# UI_BUTTON_LED.net
KiCad netlist of a schematic drawn in Altium Designer
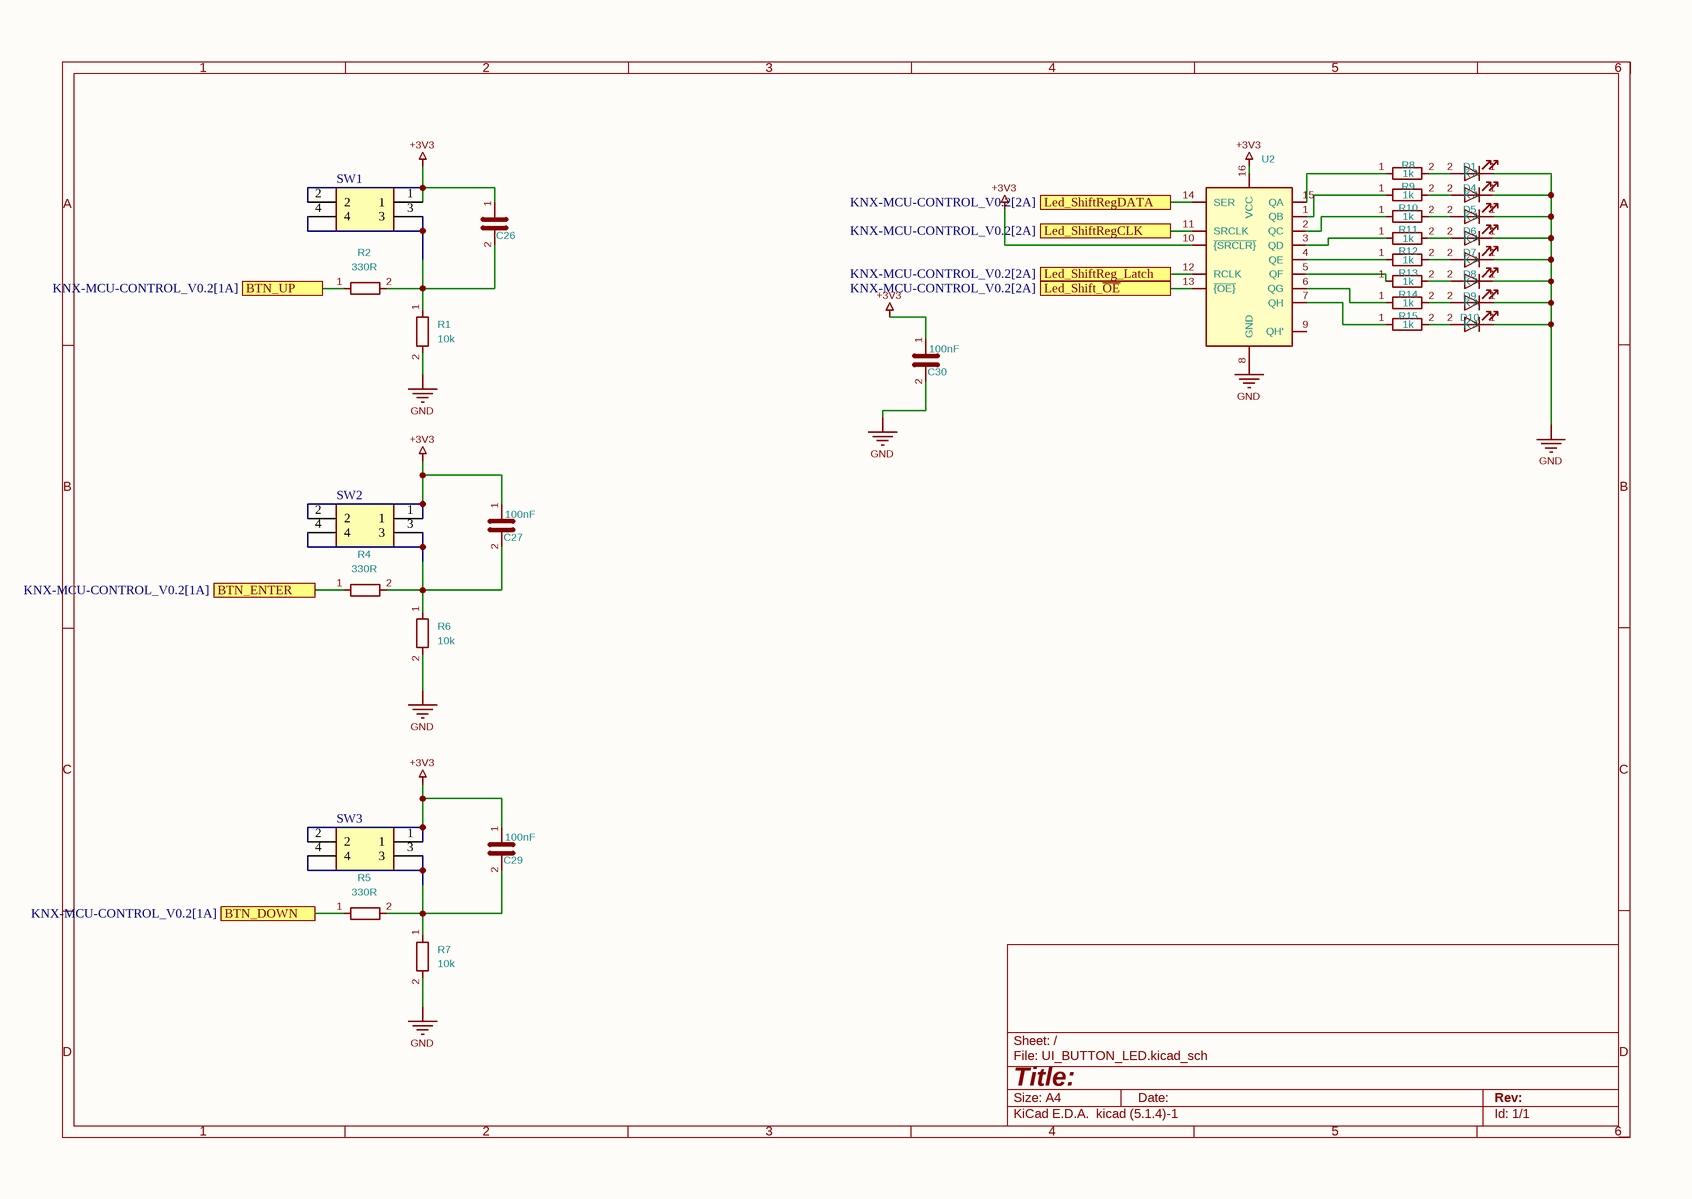
[diagram p0: UI_BUTTON_LED.SchDoc]

(export (version "E")
  (design (tool "Eeschema 10.0.6"))
  (components
    (comp (ref "C26")
      (value "100nF")
      (footprint "C_0603_1608Metric")
      (fields
        (field (name "MANUFACTURER PART NUMBER") "CC0603KRX7R9BB104")
        (field (name "MANUFACTURER") "YAGEO")
      )
      (libsource (lib "*") (part "C_3"))
    )
    (comp (ref "C27")
      (value "100nF")
      (footprint "C_0603_1608Metric")
      (fields
        (field (name "MANUFACTURER PART NUMBER") "CC0603KRX7R9BB104")
        (field (name "MANUFACTURER") "YAGEO")
      )
      (libsource (lib "*") (part "C_3"))
    )
    (comp (ref "C29")
      (value "100nF")
      (footprint "C_0603_1608Metric")
      (fields
        (field (name "MANUFACTURER PART NUMBER") "CC0603KRX7R9BB104")
        (field (name "MANUFACTURER") "YAGEO")
      )
      (libsource (lib "*") (part "C_3"))
    )
    (comp (ref "C30")
      (value "100nF")
      (footprint "C_0603_1608Metric")
      (fields
        (field (name "MANUFACTURER PART NUMBER") "CC0603KRX7R9BB104")
        (field (name "MANUFACTURER") "YAGEO")
      )
      (libsource (lib "*") (part "C_1"))
    )
    (comp (ref "D1")
      (value "LED")
      (footprint "LED_0603_1608Metric")
      (fields
        (field (name "MANUFACTURER") "LITEON")
        (field (name "MANUFACTURER PART NUMBER") "LTST-C190KFKT-5A")
      )
      (libsource (lib "Device") (part "LED"))
    )
    (comp (ref "D4")
      (value "LED")
      (footprint "LED_0603_1608Metric")
      (fields
        (field (name "MANUFACTURER") "LITEON")
        (field (name "MANUFACTURER PART NUMBER") "LTST-C190KFKT-5A")
      )
      (libsource (lib "Device") (part "LED"))
    )
    (comp (ref "D5")
      (value "LED")
      (footprint "LED_0603_1608Metric")
      (fields
        (field (name "MANUFACTURER") "LITEON")
        (field (name "MANUFACTURER PART NUMBER") "LTST-C190KFKT-5A")
      )
      (libsource (lib "Device") (part "LED"))
    )
    (comp (ref "D6")
      (value "LED")
      (footprint "LED_0603_1608Metric")
      (fields
        (field (name "MANUFACTURER") "LITEON")
        (field (name "MANUFACTURER PART NUMBER") "LTST-C190KFKT-5A")
      )
      (libsource (lib "Device") (part "LED"))
    )
    (comp (ref "D7")
      (value "LED")
      (footprint "LED_0603_1608Metric")
      (fields
        (field (name "MANUFACTURER") "LITEON")
        (field (name "MANUFACTURER PART NUMBER") "LTST-C190KFKT-5A")
      )
      (libsource (lib "Device") (part "LED"))
    )
    (comp (ref "D8")
      (value "LED")
      (footprint "LED_0603_1608Metric")
      (fields
        (field (name "MANUFACTURER") "LITEON")
        (field (name "MANUFACTURER PART NUMBER") "LTST-C190KFKT-5A")
      )
      (libsource (lib "Device") (part "LED"))
    )
    (comp (ref "D9")
      (value "LED")
      (footprint "LED_0603_1608Metric")
      (fields
        (field (name "MANUFACTURER") "LITEON")
        (field (name "MANUFACTURER PART NUMBER") "LTST-C190KFKT-5A")
      )
      (libsource (lib "Device") (part "LED"))
    )
    (comp (ref "D10")
      (value "LED")
      (footprint "LED_0603_1608Metric")
      (fields
        (field (name "MANUFACTURER") "LITEON")
        (field (name "MANUFACTURER PART NUMBER") "LTST-C190KFKT-5A")
      )
      (libsource (lib "Device") (part "LED"))
    )
    (comp (ref "R1")
      (value "10k")
      (footprint "R_0603_1608Metric")
      (fields (field (name "MANUFACTURER") "FOJAN") (field (name "MANUFACTURER PART NUMBER") "FRC0603J103TS"))
      (libsource (lib "Device") (part "R"))
    )
    (comp (ref "R2")
      (value "330R")
      (footprint "R_0603_1608Metric")
      (fields
        (field (name "MANUFACTURER") "FOJAN")
        (field (name "MANUFACTURER PART NUMBER") "FRC0603J331 TS")
      )
      (libsource (lib "") (part "R_1"))
    )
    (comp (ref "R4")
      (value "330R")
      (footprint "R_0603_1608Metric")
      (fields
        (field (name "MANUFACTURER") "FOJAN")
        (field (name "MANUFACTURER PART NUMBER") "FRC0603J331 TS")
      )
      (libsource (lib "") (part "R_1"))
    )
    (comp (ref "R5")
      (value "330R")
      (footprint "R_0603_1608Metric")
      (fields
        (field (name "MANUFACTURER") "FOJAN")
        (field (name "MANUFACTURER PART NUMBER") "FRC0603J331 TS")
      )
      (libsource (lib "") (part "R_1"))
    )
    (comp (ref "R6")
      (value "10k")
      (footprint "R_0603_1608Metric")
      (fields (field (name "MANUFACTURER") "FOJAN") (field (name "MANUFACTURER PART NUMBER") "FRC0603J103TS"))
      (libsource (lib "Device") (part "R"))
    )
    (comp (ref "R7")
      (value "10k")
      (footprint "R_0603_1608Metric")
      (fields (field (name "MANUFACTURER") "FOJAN") (field (name "MANUFACTURER PART NUMBER") "FRC0603J103TS"))
      (libsource (lib "Device") (part "R"))
    )
    (comp (ref "R8")
      (value "1k")
      (footprint "R_0603_1608Metric")
      (fields
        (field (name "MANUFACTURER") "YAGEO")
        (field (name "MANUFACTURER PART NUMBER") "RC0603JR-071KL")
      )
      (libsource (lib "") (part "R_1"))
    )
    (comp (ref "R9")
      (value "1k")
      (footprint "R_0603_1608Metric")
      (fields
        (field (name "MANUFACTURER") "YAGEO")
        (field (name "MANUFACTURER PART NUMBER") "RC0603JR-071KL")
      )
      (libsource (lib "") (part "R_1"))
    )
    (comp (ref "R10")
      (value "1k")
      (footprint "R_0603_1608Metric")
      (fields
        (field (name "MANUFACTURER") "YAGEO")
        (field (name "MANUFACTURER PART NUMBER") "RC0603JR-071KL")
      )
      (libsource (lib "") (part "R_1"))
    )
    (comp (ref "R11")
      (value "1k")
      (footprint "R_0603_1608Metric")
      (fields
        (field (name "MANUFACTURER") "YAGEO")
        (field (name "MANUFACTURER PART NUMBER") "RC0603JR-071KL")
      )
      (libsource (lib "") (part "R_1"))
    )
    (comp (ref "R12")
      (value "1k")
      (footprint "R_0603_1608Metric")
      (fields
        (field (name "MANUFACTURER") "YAGEO")
        (field (name "MANUFACTURER PART NUMBER") "RC0603JR-071KL")
      )
      (libsource (lib "") (part "R_1"))
    )
    (comp (ref "R13")
      (value "1k")
      (footprint "R_0603_1608Metric")
      (fields
        (field (name "MANUFACTURER") "YAGEO")
        (field (name "MANUFACTURER PART NUMBER") "RC0603JR-071KL")
      )
      (libsource (lib "") (part "R_1"))
    )
    (comp (ref "R14")
      (value "1k")
      (footprint "R_0603_1608Metric")
      (fields
        (field (name "MANUFACTURER") "YAGEO")
        (field (name "MANUFACTURER PART NUMBER") "RC0603JR-071KL")
      )
      (libsource (lib "") (part "R_1"))
    )
    (comp (ref "R15")
      (value "1k")
      (footprint "R_0603_1608Metric")
      (fields
        (field (name "MANUFACTURER") "YAGEO")
        (field (name "MANUFACTURER PART NUMBER") "RC0603JR-071KL")
      )
      (libsource (lib "") (part "R_1"))
    )
    (comp (ref "SW1")
      (value "TSA06141-225B532CA-3C00")
      (footprint "SamacSys:TL1105")
      (description "Through Hole-4P,8.2x7.6mm")
      (fields (field (name "MANUFACTURER") "Khon"))
      (libsource (lib "*") (part "TL1105BF160Q"))
    )
    (comp (ref "SW2")
      (value "TSA06141-225B532CA-3C00")
      (footprint "SamacSys:TL1105")
      (description "Through Hole-4P,8.2x7.6mm")
      (fields (field (name "MANUFACTURER") "Khon"))
      (libsource (lib "*") (part "TL1105BF160Q"))
    )
    (comp (ref "SW3")
      (value "TSA06141-225B532CA-3C00")
      (footprint "SamacSys:TL1105")
      (description "Through Hole-4P,8.2x7.6mm")
      (fields (field (name "MANUFACTURER") "Khon"))
      (libsource (lib "*") (part "TL1105BF160Q"))
    )
    (comp (ref "U2")
      (value "74HC595PW,118")
      (footprint "TSSOP-16_4.4x5mm_P0.65mm")
      (fields (field (name "MANUFACTURER") "Nexperia"))
      (libsource (lib "74xx") (part "74HC595"))
    )
  )
  (nets
    (net (code "1") (name "+3V3") (class "Default")
      (node (ref "C26") (pin "1") (pinfunction "1_1") (pintype "passive"))
      (node (ref "C27") (pin "1") (pinfunction "1_1") (pintype "passive"))
      (node (ref "C29") (pin "1") (pinfunction "1_1") (pintype "passive"))
      (node (ref "C30") (pin "1") (pinfunction "1_1") (pintype "passive"))
      (node (ref "SW1") (pin "1") (pinfunction "1_1") (pintype "passive"))
      (node (ref "SW1") (pin "2") (pinfunction "2_2") (pintype "passive"))
      (node (ref "SW2") (pin "1") (pinfunction "1_1") (pintype "passive"))
      (node (ref "SW2") (pin "2") (pinfunction "2_2") (pintype "passive"))
      (node (ref "SW3") (pin "1") (pinfunction "1_1") (pintype "passive"))
      (node (ref "SW3") (pin "2") (pinfunction "2_2") (pintype "passive"))
      (node (ref "U2") (pin "10") (pinfunction "~{{SRCLR}}_10") (pintype "passive"))
      (node (ref "U2") (pin "16") (pinfunction "VCC_16") (pintype "passive"))
    )
    (net (code "2") (name "/BTN_DOWN") (class "Default")
      (node (ref "R5") (pin "1") (pinfunction "1_1") (pintype "passive"))
    )
    (net (code "3") (name "/BTN_ENTER") (class "Default")
      (node (ref "R4") (pin "1") (pinfunction "1_1") (pintype "passive"))
    )
    (net (code "4") (name "/BTN_UP") (class "Default")
      (node (ref "R2") (pin "1") (pinfunction "1_1") (pintype "passive"))
    )
    (net (code "5") (name "/Led_ShiftRegCLK") (class "Default")
      (node (ref "U2") (pin "11") (pinfunction "SRCLK_11") (pintype "passive"))
    )
    (net (code "6") (name "/Led_ShiftRegDATA") (class "Default")
      (node (ref "U2") (pin "14") (pinfunction "SER_14") (pintype "passive"))
    )
    (net (code "7") (name "/Led_ShiftReg_Latch") (class "Default")
      (node (ref "U2") (pin "12") (pinfunction "RCLK_12") (pintype "passive"))
    )
    (net (code "8") (name "/Led_Shift_~{OE}") (class "Default")
      (node (ref "U2") (pin "13") (pinfunction "~{{OE}}_13") (pintype "passive"))
    )
    (net (code "9") (name "GND") (class "Default")
      (node (ref "C30") (pin "2") (pinfunction "2_2") (pintype "passive"))
      (node (ref "D1") (pin "1") (pinfunction "K_1") (pintype "passive"))
      (node (ref "D10") (pin "1") (pinfunction "K_1") (pintype "passive"))
      (node (ref "D4") (pin "1") (pinfunction "K_1") (pintype "passive"))
      (node (ref "D5") (pin "1") (pinfunction "K_1") (pintype "passive"))
      (node (ref "D6") (pin "1") (pinfunction "K_1") (pintype "passive"))
      (node (ref "D7") (pin "1") (pinfunction "K_1") (pintype "passive"))
      (node (ref "D8") (pin "1") (pinfunction "K_1") (pintype "passive"))
      (node (ref "D9") (pin "1") (pinfunction "K_1") (pintype "passive"))
      (node (ref "R1") (pin "2") (pinfunction "2_2") (pintype "passive"))
      (node (ref "R6") (pin "2") (pinfunction "2_2") (pintype "passive"))
      (node (ref "R7") (pin "2") (pinfunction "2_2") (pintype "passive"))
      (node (ref "U2") (pin "8") (pinfunction "GND_8") (pintype "passive"))
    )
    (net (code "10") (name "Net-(C26-Pad2)") (class "Default")
      (node (ref "C26") (pin "2") (pinfunction "2_2") (pintype "passive"))
      (node (ref "R1") (pin "1") (pinfunction "1_1") (pintype "passive"))
      (node (ref "R2") (pin "2") (pinfunction "2_2") (pintype "passive"))
      (node (ref "SW1") (pin "3") (pinfunction "3_3") (pintype "passive"))
      (node (ref "SW1") (pin "4") (pinfunction "4_4") (pintype "passive"))
    )
    (net (code "11") (name "Net-(C27-Pad2)") (class "Default")
      (node (ref "C27") (pin "2") (pinfunction "2_2") (pintype "passive"))
      (node (ref "R4") (pin "2") (pinfunction "2_2") (pintype "passive"))
      (node (ref "R6") (pin "1") (pinfunction "1_1") (pintype "passive"))
      (node (ref "SW2") (pin "3") (pinfunction "3_3") (pintype "passive"))
      (node (ref "SW2") (pin "4") (pinfunction "4_4") (pintype "passive"))
    )
    (net (code "12") (name "Net-(C29-Pad2)") (class "Default")
      (node (ref "C29") (pin "2") (pinfunction "2_2") (pintype "passive"))
      (node (ref "R5") (pin "2") (pinfunction "2_2") (pintype "passive"))
      (node (ref "R7") (pin "1") (pinfunction "1_1") (pintype "passive"))
      (node (ref "SW3") (pin "3") (pinfunction "3_3") (pintype "passive"))
      (node (ref "SW3") (pin "4") (pinfunction "4_4") (pintype "passive"))
    )
    (net (code "13") (name "Net-(D1-A)") (class "Default")
      (node (ref "D1") (pin "2") (pinfunction "A_2") (pintype "passive"))
      (node (ref "R8") (pin "2") (pinfunction "2_2") (pintype "passive"))
    )
    (net (code "14") (name "Net-(D4-A)") (class "Default")
      (node (ref "D4") (pin "2") (pinfunction "A_2") (pintype "passive"))
      (node (ref "R9") (pin "2") (pinfunction "2_2") (pintype "passive"))
    )
    (net (code "15") (name "Net-(D5-A)") (class "Default")
      (node (ref "D5") (pin "2") (pinfunction "A_2") (pintype "passive"))
      (node (ref "R10") (pin "2") (pinfunction "2_2") (pintype "passive"))
    )
    (net (code "16") (name "Net-(D6-A)") (class "Default")
      (node (ref "D6") (pin "2") (pinfunction "A_2") (pintype "passive"))
      (node (ref "R11") (pin "2") (pinfunction "2_2") (pintype "passive"))
    )
    (net (code "17") (name "Net-(D7-A)") (class "Default")
      (node (ref "D7") (pin "2") (pinfunction "A_2") (pintype "passive"))
      (node (ref "R12") (pin "2") (pinfunction "2_2") (pintype "passive"))
    )
    (net (code "18") (name "Net-(D8-A)") (class "Default")
      (node (ref "D8") (pin "2") (pinfunction "A_2") (pintype "passive"))
      (node (ref "R13") (pin "2") (pinfunction "2_2") (pintype "passive"))
    )
    (net (code "19") (name "Net-(D9-A)") (class "Default")
      (node (ref "D9") (pin "2") (pinfunction "A_2") (pintype "passive"))
      (node (ref "R14") (pin "2") (pinfunction "2_2") (pintype "passive"))
    )
    (net (code "20") (name "Net-(D10-A)") (class "Default")
      (node (ref "D10") (pin "2") (pinfunction "A_2") (pintype "passive"))
      (node (ref "R15") (pin "2") (pinfunction "2_2") (pintype "passive"))
    )
    (net (code "21") (name "Net-(U2-QA)") (class "Default")
      (node (ref "R8") (pin "1") (pinfunction "1_1") (pintype "passive"))
      (node (ref "U2") (pin "15") (pinfunction "QA_15") (pintype "passive"))
    )
    (net (code "22") (name "Net-(U2-QB)") (class "Default")
      (node (ref "R9") (pin "1") (pinfunction "1_1") (pintype "passive"))
      (node (ref "U2") (pin "1") (pinfunction "QB_1") (pintype "passive"))
    )
    (net (code "23") (name "Net-(U2-QC)") (class "Default")
      (node (ref "R10") (pin "1") (pinfunction "1_1") (pintype "passive"))
      (node (ref "U2") (pin "2") (pinfunction "QC_2") (pintype "passive"))
    )
    (net (code "24") (name "Net-(U2-QD)") (class "Default")
      (node (ref "R11") (pin "1") (pinfunction "1_1") (pintype "passive"))
      (node (ref "U2") (pin "3") (pinfunction "QD_3") (pintype "passive"))
    )
    (net (code "25") (name "Net-(U2-QE)") (class "Default")
      (node (ref "R12") (pin "1") (pinfunction "1_1") (pintype "passive"))
      (node (ref "U2") (pin "4") (pinfunction "QE_4") (pintype "passive"))
    )
    (net (code "26") (name "Net-(U2-QF)") (class "Default")
      (node (ref "R13") (pin "1") (pinfunction "1_1") (pintype "passive"))
      (node (ref "U2") (pin "5") (pinfunction "QF_5") (pintype "passive"))
    )
    (net (code "27") (name "Net-(U2-QG)") (class "Default")
      (node (ref "R14") (pin "1") (pinfunction "1_1") (pintype "passive"))
      (node (ref "U2") (pin "6") (pinfunction "QG_6") (pintype "passive"))
    )
    (net (code "28") (name "Net-(U2-QH)") (class "Default")
      (node (ref "R15") (pin "1") (pinfunction "1_1") (pintype "passive"))
      (node (ref "U2") (pin "7") (pinfunction "QH_7") (pintype "passive"))
    )
    (net (code "29") (name "unconnected-(U2-QH'-Pad9)") (class "Default")
      (node (ref "U2") (pin "9") (pinfunction "QH'_9") (pintype "passive"))
    )
  )
)
